# main_board_CHM.net
KiCad netlist of a schematic drawn in Altium Designer
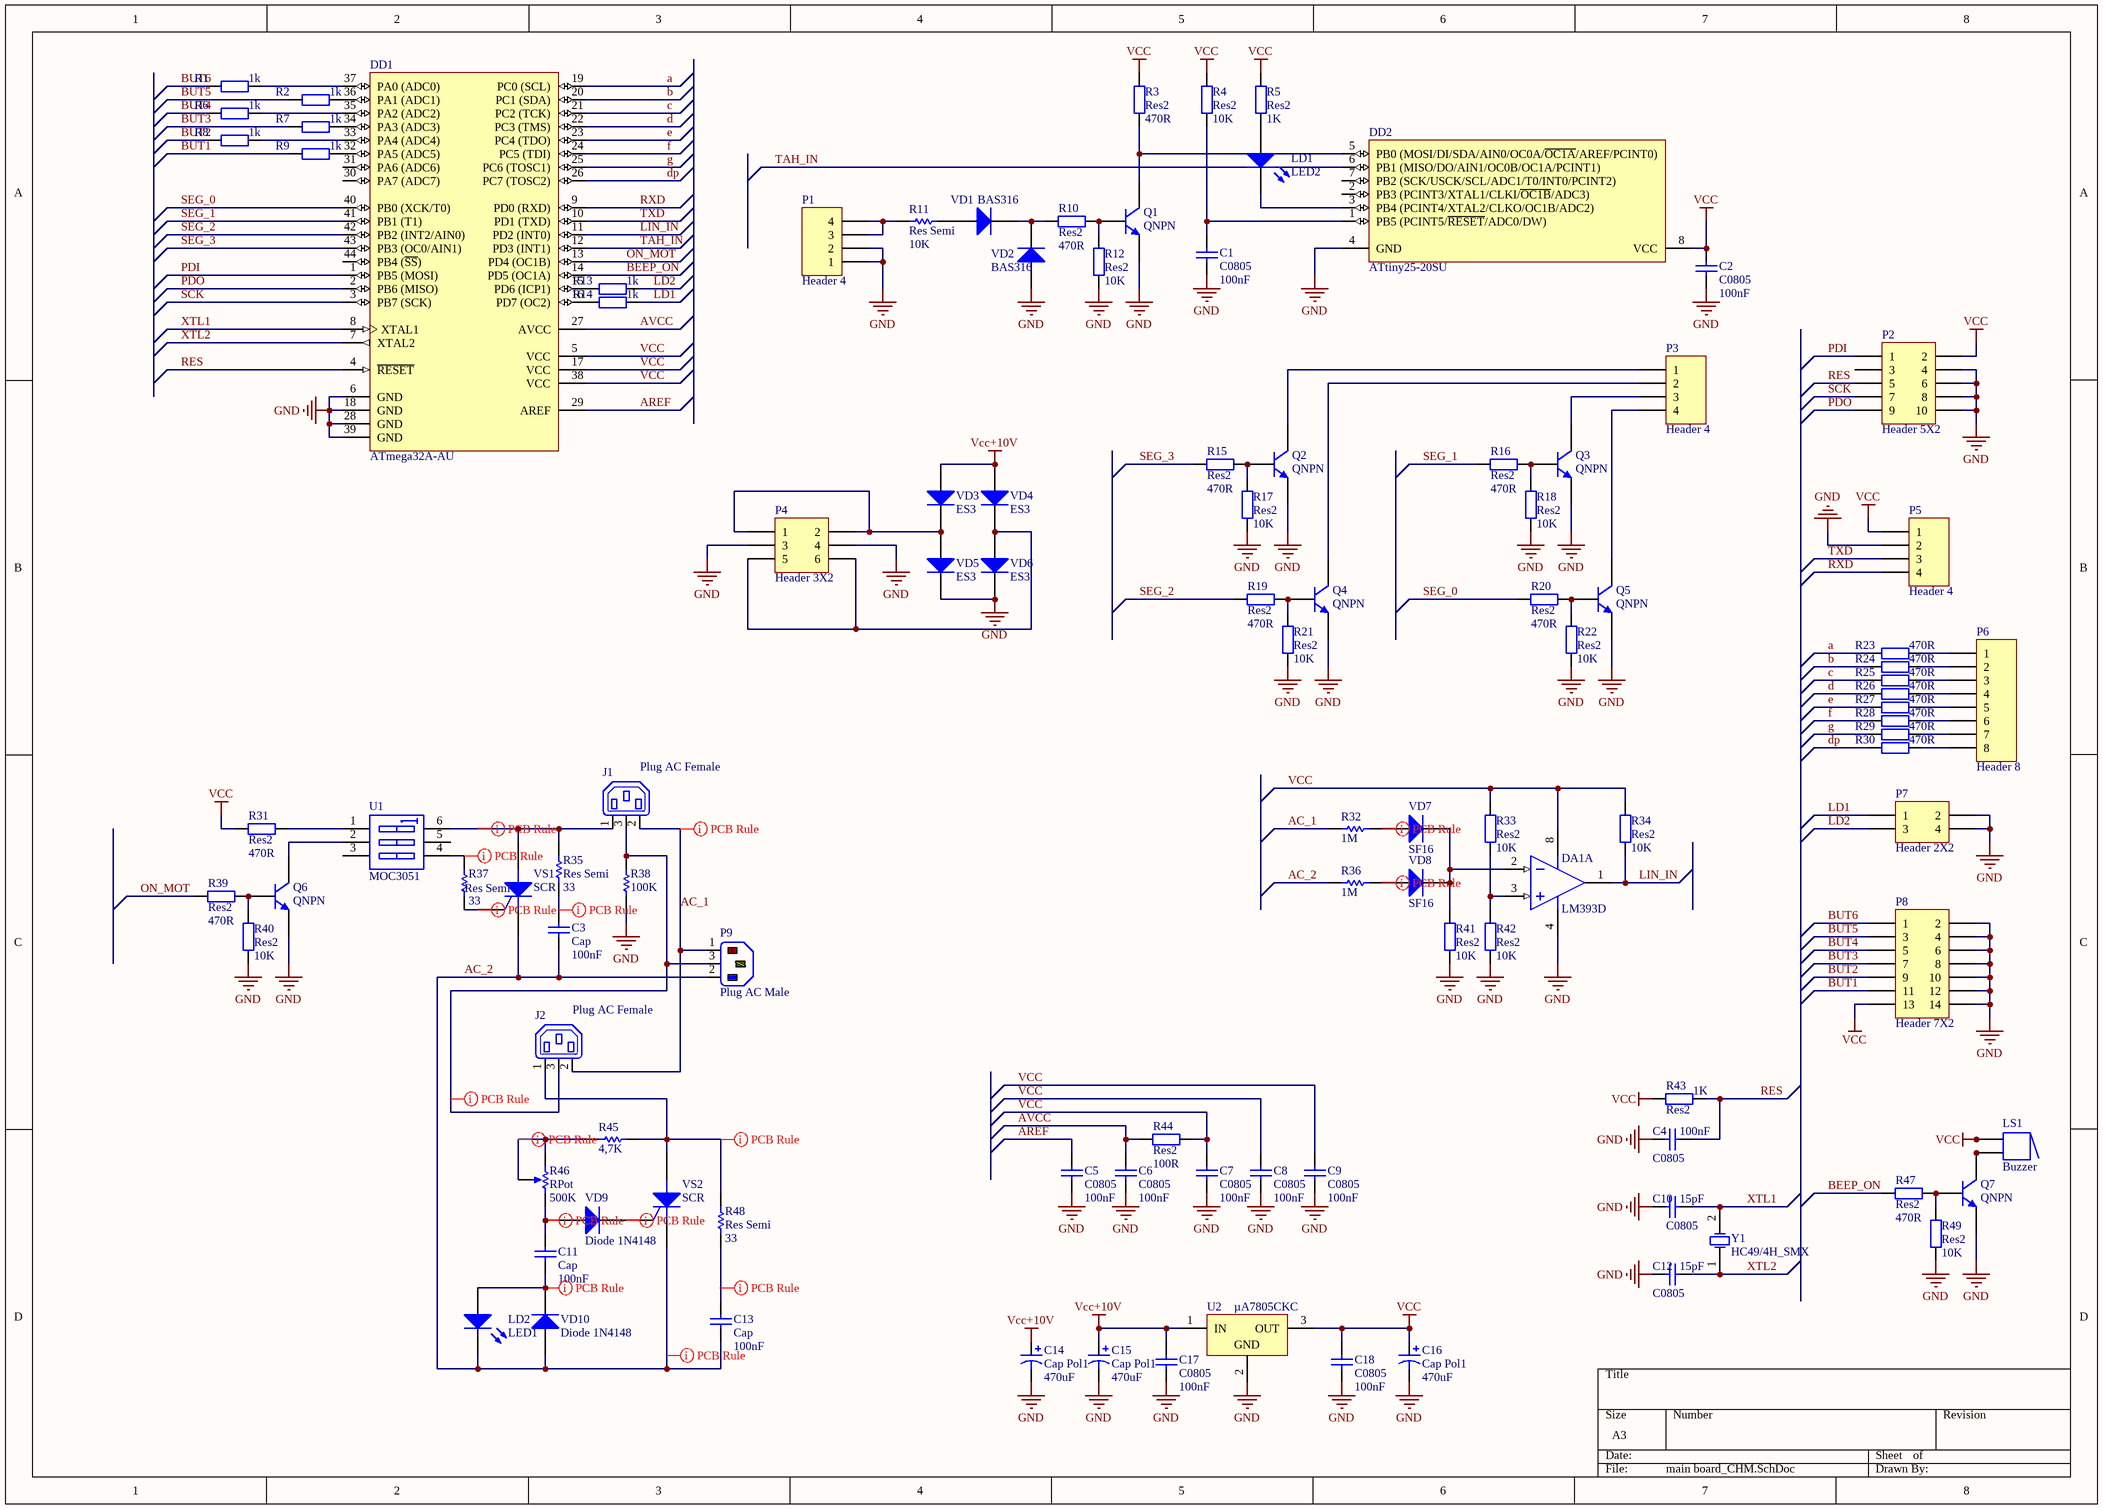
[diagram p0: main board_CHM.SchDoc]

(export (version "E")
  (design (tool "Eeschema 10.0.6"))
  (components
    (comp (ref "C1")
      (value "C0805")
      (footprint "0805")
      (description "Ceramic Chip Capacitor - Standard")
      (fields (field (name "ALTIUM_VALUE") "100nF"))
      (libsource (lib "KEMET Chip Capacitor") (part "C0805"))
    )
    (comp (ref "C2")
      (value "C0805")
      (footprint "0805")
      (description "Ceramic Chip Capacitor - Standard")
      (fields (field (name "ALTIUM_VALUE") "100nF"))
      (libsource (lib "KEMET Chip Capacitor") (part "C0805"))
    )
    (comp (ref "C3")
      (value "Cap")
      (footprint "RAD-0.3")
      (description "Capacitor")
      (fields (field (name "ALTIUM_VALUE") "100nF"))
      (libsource (lib "Miscellaneous Devices") (part "Cap"))
    )
    (comp (ref "C4")
      (value "C0805")
      (footprint "0805")
      (description "Ceramic Chip Capacitor - Standard")
      (fields (field (name "ALTIUM_VALUE") "100nF"))
      (libsource (lib "KEMET Chip Capacitor") (part "C0805"))
    )
    (comp (ref "C5")
      (value "C0805")
      (footprint "0805")
      (description "Ceramic Chip Capacitor - Standard")
      (fields (field (name "ALTIUM_VALUE") "100nF"))
      (libsource (lib "KEMET Chip Capacitor") (part "C0805"))
    )
    (comp (ref "C6")
      (value "C0805")
      (footprint "0805")
      (description "Ceramic Chip Capacitor - Standard")
      (fields (field (name "ALTIUM_VALUE") "100nF"))
      (libsource (lib "KEMET Chip Capacitor") (part "C0805"))
    )
    (comp (ref "C7")
      (value "C0805")
      (footprint "0805")
      (description "Ceramic Chip Capacitor - Standard")
      (fields (field (name "ALTIUM_VALUE") "100nF"))
      (libsource (lib "KEMET Chip Capacitor") (part "C0805"))
    )
    (comp (ref "C8")
      (value "C0805")
      (footprint "0805")
      (description "Ceramic Chip Capacitor - Standard")
      (fields (field (name "ALTIUM_VALUE") "100nF"))
      (libsource (lib "KEMET Chip Capacitor") (part "C0805"))
    )
    (comp (ref "C9")
      (value "C0805")
      (footprint "0805")
      (description "Ceramic Chip Capacitor - Standard")
      (fields (field (name "ALTIUM_VALUE") "100nF"))
      (libsource (lib "KEMET Chip Capacitor") (part "C0805"))
    )
    (comp (ref "C10")
      (value "C0805")
      (footprint "0805")
      (description "Ceramic Chip Capacitor - Standard")
      (fields (field (name "ALTIUM_VALUE") "15pF"))
      (libsource (lib "KEMET Chip Capacitor") (part "C0805"))
    )
    (comp (ref "C11")
      (value "Cap")
      (footprint "RAD-0.3")
      (description "Capacitor")
      (fields (field (name "ALTIUM_VALUE") "100nF"))
      (libsource (lib "Miscellaneous Devices") (part "Cap"))
    )
    (comp (ref "C12")
      (value "C0805")
      (footprint "0805")
      (description "Ceramic Chip Capacitor - Standard")
      (fields (field (name "ALTIUM_VALUE") "15pF"))
      (libsource (lib "KEMET Chip Capacitor") (part "C0805"))
    )
    (comp (ref "C13")
      (value "Cap")
      (footprint "RAD-0.3")
      (description "Capacitor")
      (fields (field (name "ALTIUM_VALUE") "100nF"))
      (libsource (lib "Miscellaneous Devices") (part "Cap"))
    )
    (comp (ref "C14")
      (value "Cap Pol1")
      (footprint "RB5-10.5")
      (description "Polarized Capacitor (Radial)")
      (fields (field (name "ALTIUM_VALUE") "470uF"))
      (libsource (lib "Miscellaneous Devices") (part "Cap Pol1"))
    )
    (comp (ref "C15")
      (value "Cap Pol1")
      (footprint "RB5-10.5")
      (description "Polarized Capacitor (Radial)")
      (fields (field (name "ALTIUM_VALUE") "470uF"))
      (libsource (lib "Miscellaneous Devices") (part "Cap Pol1"))
    )
    (comp (ref "C16")
      (value "Cap Pol1")
      (footprint "RB5-10.5")
      (description "Polarized Capacitor (Radial)")
      (fields (field (name "ALTIUM_VALUE") "470uF"))
      (libsource (lib "Miscellaneous Devices") (part "Cap Pol1"))
    )
    (comp (ref "C17")
      (value "C0805")
      (footprint "0805")
      (description "Ceramic Chip Capacitor - Standard")
      (fields (field (name "ALTIUM_VALUE") "100nF"))
      (libsource (lib "KEMET Chip Capacitor") (part "C0805"))
    )
    (comp (ref "C18")
      (value "C0805")
      (footprint "0805")
      (description "Ceramic Chip Capacitor - Standard")
      (fields (field (name "ALTIUM_VALUE") "100nF"))
      (libsource (lib "KEMET Chip Capacitor") (part "C0805"))
    )
    (comp (ref "DA1")
      (value "LM393D")
      (footprint "SO8_L")
      (description "Low-Power Dual Voltage Comparator")
      (libsource (lib "ST Analog Comparator") (part "LM393D"))
    )
    (comp (ref "DD1")
      (value "ATmega32A-AU")
      (footprint "44A_N")
      (libsource (lib "Atmel Microcontroller 8-Bit megaAVR") (part "ATmega32A-AU"))
    )
    (comp (ref "DD2")
      (value "ATtiny25-20SU")
      (footprint "8S2_N")
      (libsource (lib "Atmel Microcontroller 8-Bit tinyAVR") (part "ATtiny25-20SU"))
    )
    (comp (ref "J1")
      (value "Plug AC Female")
      (footprint "SUPER-247")
      (description "IEC Mains Power Outlet, EN60 320-2-2 F Class I, PC Flange Rear Mount, Chassis Socket")
      (libsource (lib "Miscellaneous Connectors") (part "Plug AC Female"))
    )
    (comp (ref "J2")
      (value "Plug AC Female")
      (footprint "Super-TO-247AC")
      (description "IEC Mains Power Outlet, EN60 320-2-2 F Class I, PC Flange Rear Mount, Chassis Socket")
      (libsource (lib "Miscellaneous Connectors") (part "Plug AC Female"))
    )
    (comp (ref "LD1")
      (value "LED2")
      (footprint "3.2X1.6X1.1")
      (description "Typical RED, GREEN, YELLOW, AMBER GaAs LED")
      (libsource (lib "Miscellaneous Devices") (part "LED2"))
    )
    (comp (ref "LD2")
      (value "LED1")
      (footprint "HDR1X2")
      (description "Typical RED GaAs LED")
      (libsource (lib "Miscellaneous Devices") (part "LED1"))
    )
    (comp (ref "LS1")
      (value "Buzzer")
      (footprint "ABSM-1574")
      (description "Magnetic Transducer Buzzer")
      (libsource (lib "Miscellaneous Devices") (part "Buzzer"))
    )
    (comp (ref "P1")
      (value "Header 4")
      (footprint "HDR1X4")
      (description "Header, 4-Pin")
      (libsource (lib "") (part "Header 4_1"))
    )
    (comp (ref "P2")
      (value "Header 5X2")
      (footprint "HDR2X5")
      (description "Header, 5-Pin, Dual row")
      (libsource (lib "Miscellaneous Connectors") (part "Header 5X2"))
    )
    (comp (ref "P3")
      (value "Header 4")
      (footprint "HDR1X4")
      (description "Header, 4-Pin")
      (libsource (lib "Miscellaneous Connectors") (part "Header 4"))
    )
    (comp (ref "P4")
      (value "Header 3X2")
      (footprint "HDR2X3")
      (description "Header, 3-Pin, Dual row")
      (libsource (lib "Miscellaneous Connectors") (part "Header 3X2"))
    )
    (comp (ref "P5")
      (value "Header 4")
      (footprint "HDR1X4")
      (description "Header, 4-Pin")
      (libsource (lib "Miscellaneous Connectors") (part "Header 4"))
    )
    (comp (ref "P6")
      (value "Header 8")
      (footprint "HDR1X8")
      (description "Header, 8-Pin")
      (libsource (lib "Miscellaneous Connectors") (part "Header 8"))
    )
    (comp (ref "P7")
      (value "Header 2X2")
      (footprint "HDR2X2")
      (description "Header, 2-Pin, Dual row")
      (libsource (lib "Miscellaneous Connectors") (part "Header 2X2"))
    )
    (comp (ref "P8")
      (value "Header 7X2")
      (footprint "HDR2X7")
      (description "Header, 7-Pin, Dual row")
      (libsource (lib "Miscellaneous Connectors") (part "Header 7X2"))
    )
    (comp (ref "P9")
      (value "Plug AC Male")
      (footprint "Super-TO-247AC")
      (description "IEC Mains Power Inlet, EN60 320-1 C14 Class I Cold Condition, PC Flange Rear Mount, Chassis Plug")
      (libsource (lib "Miscellaneous Connectors") (part "Plug AC Male"))
    )
    (comp (ref "Q1")
      (value "QNPN")
      (footprint "SOT23_M")
      (description "NPN Bipolar Transistor")
      (libsource (lib "Miscellaneous Devices") (part "QNPN"))
    )
    (comp (ref "Q2")
      (value "QNPN")
      (footprint "SOT23_M")
      (description "NPN Bipolar Transistor")
      (libsource (lib "Miscellaneous Devices") (part "QNPN"))
    )
    (comp (ref "Q3")
      (value "QNPN")
      (footprint "SOT23_M")
      (description "NPN Bipolar Transistor")
      (libsource (lib "Miscellaneous Devices") (part "QNPN"))
    )
    (comp (ref "Q4")
      (value "QNPN")
      (footprint "SOT23_M")
      (description "NPN Bipolar Transistor")
      (libsource (lib "Miscellaneous Devices") (part "QNPN"))
    )
    (comp (ref "Q5")
      (value "QNPN")
      (footprint "SOT23_M")
      (description "NPN Bipolar Transistor")
      (libsource (lib "Miscellaneous Devices") (part "QNPN"))
    )
    (comp (ref "Q6")
      (value "QNPN")
      (footprint "SOT23_M")
      (description "NPN Bipolar Transistor")
      (libsource (lib "Miscellaneous Devices") (part "QNPN"))
    )
    (comp (ref "Q7")
      (value "QNPN")
      (footprint "SOT23_M")
      (description "NPN Bipolar Transistor")
      (libsource (lib "Miscellaneous Devices") (part "QNPN"))
    )
    (comp (ref "R1")
      (value "1k")
      (footprint "6-0805_N")
      (description "Resistor")
      (fields (field (name "Comment") "Res2"))
      (libsource (lib "Miscellaneous Devices") (part "Res2"))
    )
    (comp (ref "R2")
      (value "1k")
      (footprint "6-0805_N")
      (description "Resistor")
      (fields (field (name "Comment") "Res2"))
      (libsource (lib "Miscellaneous Devices") (part "Res2"))
    )
    (comp (ref "R3")
      (value "Res2")
      (footprint "6-0805_N")
      (description "Resistor")
      (fields (field (name "ALTIUM_VALUE") "470R"))
      (libsource (lib "") (part "Res2_1"))
    )
    (comp (ref "R4")
      (value "Res2")
      (footprint "6-0805_N")
      (description "Resistor")
      (fields (field (name "ALTIUM_VALUE") "10K"))
      (libsource (lib "") (part "Res2_1"))
    )
    (comp (ref "R5")
      (value "Res2")
      (footprint "6-0805_N")
      (description "Resistor")
      (fields (field (name "ALTIUM_VALUE") "1K"))
      (libsource (lib "") (part "Res2_1"))
    )
    (comp (ref "R6")
      (value "1k")
      (footprint "6-0805_N")
      (description "Resistor")
      (fields (field (name "Comment") "Res2"))
      (libsource (lib "Miscellaneous Devices") (part "Res2"))
    )
    (comp (ref "R7")
      (value "1k")
      (footprint "6-0805_N")
      (description "Resistor")
      (fields (field (name "Comment") "Res2"))
      (libsource (lib "Miscellaneous Devices") (part "Res2"))
    )
    (comp (ref "R8")
      (value "1k")
      (footprint "6-0805_N")
      (description "Resistor")
      (fields (field (name "Comment") "Res2"))
      (libsource (lib "Miscellaneous Devices") (part "Res2"))
    )
    (comp (ref "R9")
      (value "1k")
      (footprint "6-0805_N")
      (description "Resistor")
      (fields (field (name "Comment") "Res2"))
      (libsource (lib "Miscellaneous Devices") (part "Res2"))
    )
    (comp (ref "R10")
      (value "Res2")
      (footprint "6-0805_N")
      (description "Resistor")
      (fields (field (name "ALTIUM_VALUE") "470R"))
      (libsource (lib "Miscellaneous Devices") (part "Res2"))
    )
    (comp (ref "R11")
      (value "Res Semi")
      (footprint "AXIAL-0.5")
      (description "Semiconductor Resistor")
      (fields (field (name "ALTIUM_VALUE") "10K"))
      (libsource (lib "Miscellaneous Devices") (part "Res Semi"))
    )
    (comp (ref "R12")
      (value "Res2")
      (footprint "6-0805_N")
      (description "Resistor")
      (fields (field (name "ALTIUM_VALUE") "10K"))
      (libsource (lib "") (part "Res2_1"))
    )
    (comp (ref "R13")
      (value "1k")
      (footprint "6-0805_N")
      (description "Resistor")
      (fields (field (name "Comment") "Res2"))
      (libsource (lib "Miscellaneous Devices") (part "Res2"))
    )
    (comp (ref "R14")
      (value "1k")
      (footprint "6-0805_N")
      (description "Resistor")
      (fields (field (name "Comment") "Res2"))
      (libsource (lib "Miscellaneous Devices") (part "Res2"))
    )
    (comp (ref "R15")
      (value "Res2")
      (footprint "6-0805_N")
      (description "Resistor")
      (fields (field (name "ALTIUM_VALUE") "470R"))
      (libsource (lib "Miscellaneous Devices") (part "Res2"))
    )
    (comp (ref "R16")
      (value "Res2")
      (footprint "6-0805_N")
      (description "Resistor")
      (fields (field (name "ALTIUM_VALUE") "470R"))
      (libsource (lib "Miscellaneous Devices") (part "Res2"))
    )
    (comp (ref "R17")
      (value "Res2")
      (footprint "6-0805_N")
      (description "Resistor")
      (fields (field (name "ALTIUM_VALUE") "10K"))
      (libsource (lib "") (part "Res2_1"))
    )
    (comp (ref "R18")
      (value "Res2")
      (footprint "6-0805_N")
      (description "Resistor")
      (fields (field (name "ALTIUM_VALUE") "10K"))
      (libsource (lib "") (part "Res2_1"))
    )
    (comp (ref "R19")
      (value "Res2")
      (footprint "6-0805_N")
      (description "Resistor")
      (fields (field (name "ALTIUM_VALUE") "470R"))
      (libsource (lib "Miscellaneous Devices") (part "Res2"))
    )
    (comp (ref "R20")
      (value "Res2")
      (footprint "6-0805_N")
      (description "Resistor")
      (fields (field (name "ALTIUM_VALUE") "470R"))
      (libsource (lib "Miscellaneous Devices") (part "Res2"))
    )
    (comp (ref "R21")
      (value "Res2")
      (footprint "6-0805_N")
      (description "Resistor")
      (fields (field (name "ALTIUM_VALUE") "10K"))
      (libsource (lib "") (part "Res2_1"))
    )
    (comp (ref "R22")
      (value "Res2")
      (footprint "6-0805_N")
      (description "Resistor")
      (fields (field (name "ALTIUM_VALUE") "10K"))
      (libsource (lib "") (part "Res2_1"))
    )
    (comp (ref "R23")
      (value "470R")
      (footprint "6-0805_N")
      (description "Resistor")
      (fields (field (name "Comment") "Res2"))
      (libsource (lib "Miscellaneous Devices") (part "Res2"))
    )
    (comp (ref "R24")
      (value "470R")
      (footprint "6-0805_N")
      (description "Resistor")
      (fields (field (name "Comment") "Res2"))
      (libsource (lib "Miscellaneous Devices") (part "Res2"))
    )
    (comp (ref "R25")
      (value "470R")
      (footprint "6-0805_N")
      (description "Resistor")
      (fields (field (name "Comment") "Res2"))
      (libsource (lib "Miscellaneous Devices") (part "Res2"))
    )
    (comp (ref "R26")
      (value "470R")
      (footprint "6-0805_N")
      (description "Resistor")
      (fields (field (name "Comment") "Res2"))
      (libsource (lib "Miscellaneous Devices") (part "Res2"))
    )
    (comp (ref "R27")
      (value "470R")
      (footprint "6-0805_N")
      (description "Resistor")
      (fields (field (name "Comment") "Res2"))
      (libsource (lib "Miscellaneous Devices") (part "Res2"))
    )
    (comp (ref "R28")
      (value "470R")
      (footprint "6-0805_N")
      (description "Resistor")
      (fields (field (name "Comment") "Res2"))
      (libsource (lib "Miscellaneous Devices") (part "Res2"))
    )
    (comp (ref "R29")
      (value "470R")
      (footprint "6-0805_N")
      (description "Resistor")
      (fields (field (name "Comment") "Res2"))
      (libsource (lib "Miscellaneous Devices") (part "Res2"))
    )
    (comp (ref "R30")
      (value "470R")
      (footprint "6-0805_N")
      (description "Resistor")
      (fields (field (name "Comment") "Res2"))
      (libsource (lib "Miscellaneous Devices") (part "Res2"))
    )
    (comp (ref "R31")
      (value "Res2")
      (footprint "6-0805_N")
      (description "Resistor")
      (fields (field (name "ALTIUM_VALUE") "470R"))
      (libsource (lib "Miscellaneous Devices") (part "Res2"))
    )
    (comp (ref "R32")
      (value "1M")
      (footprint "AXIAL-0.5")
      (description "Semiconductor Resistor")
      (fields (field (name "Comment") "Res Semi"))
      (libsource (lib "Miscellaneous Devices") (part "Res Semi"))
    )
    (comp (ref "R33")
      (value "Res2")
      (footprint "6-0805_N")
      (description "Resistor")
      (fields (field (name "ALTIUM_VALUE") "10K"))
      (libsource (lib "") (part "Res2_1"))
    )
    (comp (ref "R34")
      (value "Res2")
      (footprint "6-0805_N")
      (description "Resistor")
      (fields (field (name "ALTIUM_VALUE") "10K"))
      (libsource (lib "") (part "Res2_1"))
    )
    (comp (ref "R35")
      (value "Res Semi")
      (footprint "AXIAL-0.5")
      (description "Semiconductor Resistor")
      (fields (field (name "ALTIUM_VALUE") "33"))
      (libsource (lib "Miscellaneous Devices") (part "Res Semi"))
    )
    (comp (ref "R36")
      (value "1M")
      (footprint "AXIAL-0.5")
      (description "Semiconductor Resistor")
      (fields (field (name "Comment") "Res Semi"))
      (libsource (lib "Miscellaneous Devices") (part "Res Semi"))
    )
    (comp (ref "R37")
      (value "Res Semi")
      (footprint "AXIAL-0.5")
      (description "Semiconductor Resistor")
      (fields (field (name "ALTIUM_VALUE") "33"))
      (libsource (lib "Miscellaneous Devices") (part "Res Semi"))
    )
    (comp (ref "R38")
      (value "100K")
      (footprint "AXIAL-0.5")
      (description "Semiconductor Resistor")
      (fields (field (name "Comment") "Res Semi"))
      (libsource (lib "Miscellaneous Devices") (part "Res Semi"))
    )
    (comp (ref "R39")
      (value "Res2")
      (footprint "6-0805_N")
      (description "Resistor")
      (fields (field (name "ALTIUM_VALUE") "470R"))
      (libsource (lib "Miscellaneous Devices") (part "Res2"))
    )
    (comp (ref "R40")
      (value "Res2")
      (footprint "6-0805_N")
      (description "Resistor")
      (fields (field (name "ALTIUM_VALUE") "10K"))
      (libsource (lib "") (part "Res2_1"))
    )
    (comp (ref "R41")
      (value "Res2")
      (footprint "6-0805_N")
      (description "Resistor")
      (fields (field (name "ALTIUM_VALUE") "10K"))
      (libsource (lib "") (part "Res2_1"))
    )
    (comp (ref "R42")
      (value "Res2")
      (footprint "6-0805_N")
      (description "Resistor")
      (fields (field (name "ALTIUM_VALUE") "10K"))
      (libsource (lib "") (part "Res2_1"))
    )
    (comp (ref "R43")
      (value "Res2")
      (footprint "6-0805_N")
      (description "Resistor")
      (fields (field (name "ALTIUM_VALUE") "1K"))
      (libsource (lib "Miscellaneous Devices") (part "Res2"))
    )
    (comp (ref "R44")
      (value "Res2")
      (footprint "6-0805_N")
      (description "Resistor")
      (fields (field (name "ALTIUM_VALUE") "100R"))
      (libsource (lib "Miscellaneous Devices") (part "Res2"))
    )
    (comp (ref "R45")
      (value "4,7K")
      (footprint "AXIAL-0.5")
      (description "Semiconductor Resistor")
      (fields (field (name "Comment") "Res Semi"))
      (libsource (lib "Miscellaneous Devices") (part "Res Semi"))
    )
    (comp (ref "R46")
      (value "RPot")
      (footprint "VR5")
      (description "Potentiometer")
      (fields (field (name "ALTIUM_VALUE") "500K"))
      (libsource (lib "Miscellaneous Devices") (part "RPot"))
    )
    (comp (ref "R47")
      (value "Res2")
      (footprint "6-0805_N")
      (description "Resistor")
      (fields (field (name "ALTIUM_VALUE") "470R"))
      (libsource (lib "Miscellaneous Devices") (part "Res2"))
    )
    (comp (ref "R48")
      (value "Res Semi")
      (footprint "AXIAL-0.5")
      (description "Semiconductor Resistor")
      (fields (field (name "ALTIUM_VALUE") "33"))
      (libsource (lib "Miscellaneous Devices") (part "Res Semi"))
    )
    (comp (ref "R49")
      (value "Res2")
      (footprint "6-0805_N")
      (description "Resistor")
      (fields (field (name "ALTIUM_VALUE") "10K"))
      (libsource (lib "") (part "Res2_1"))
    )
    (comp (ref "U1")
      (value "MOC3051")
      (footprint "DIP-6")
      (description "DIP Switch, 3 Position, SPST")
      (libsource (lib "Miscellaneous Devices") (part "SW DIP-3"))
    )
    (comp (ref "U2")
      (value "µA7805CKC")
      (footprint "KC03")
      (description "Positive-Voltage Regulator")
      (libsource (lib "TI Power Mgt Voltage Regulator") (part "µA7805CKC"))
    )
    (comp (ref "VD1")
      (value "BAS316")
      (footprint "SOD-323")
      (description "Silicon RF Switching Diode for VHF Band Switching in TV/VTR Tuners")
      (libsource (lib "Infineon Discrete Diode") (part "BA592"))
    )
    (comp (ref "VD2")
      (value "BAS316")
      (footprint "SOD-323")
      (description "Silicon RF Switching Diode for VHF Band Switching in TV/VTR Tuners")
      (libsource (lib "Infineon Discrete Diode") (part "BA592"))
    )
    (comp (ref "VD3")
      (value "ES3")
      (footprint "SMC")
      (description "Silicon RF Switching Diode for VHF Band Switching in TV/VTR Tuners")
      (libsource (lib "Infineon Discrete Diode") (part "BA592"))
    )
    (comp (ref "VD4")
      (value "ES3")
      (footprint "SMC")
      (description "Silicon RF Switching Diode for VHF Band Switching in TV/VTR Tuners")
      (libsource (lib "Infineon Discrete Diode") (part "BA592"))
    )
    (comp (ref "VD5")
      (value "ES3")
      (footprint "SMC")
      (description "Silicon RF Switching Diode for VHF Band Switching in TV/VTR Tuners")
      (libsource (lib "Infineon Discrete Diode") (part "BA592"))
    )
    (comp (ref "VD6")
      (value "ES3")
      (footprint "SMC")
      (description "Silicon RF Switching Diode for VHF Band Switching in TV/VTR Tuners")
      (libsource (lib "Infineon Discrete Diode") (part "BA592"))
    )
    (comp (ref "VD7")
      (value "SF16")
      (footprint "DO-41")
      (description "1 Amp General Purpose Rectifier")
      (libsource (lib "Miscellaneous Devices") (part "Diode 1N4001"))
    )
    (comp (ref "VD8")
      (value "SF16")
      (footprint "DO-41")
      (description "1 Amp General Purpose Rectifier")
      (libsource (lib "Miscellaneous Devices") (part "Diode 1N4001"))
    )
    (comp (ref "VD9")
      (value "Diode 1N4148")
      (footprint "DO-35")
      (description "High Conductance Fast Diode")
      (libsource (lib "Miscellaneous Devices") (part "Diode 1N4148"))
    )
    (comp (ref "VD10")
      (value "Diode 1N4148")
      (footprint "DO-35")
      (description "High Conductance Fast Diode")
      (libsource (lib "Miscellaneous Devices") (part "Diode 1N4148"))
    )
    (comp (ref "VS1")
      (value "SCR")
      (footprint "Super-TO-247AC")
      (description "Silicon Controlled Rectifier")
      (libsource (lib "Miscellaneous Devices") (part "SCR"))
    )
    (comp (ref "VS2")
      (value "SCR")
      (footprint "Super-TO-247AC")
      (description "Silicon Controlled Rectifier")
      (libsource (lib "Miscellaneous Devices") (part "SCR"))
    )
    (comp (ref "Y1")
      (value "HC49/4H_SMX")
      (footprint "HC49/4H_SMX")
      (description "Surface Mount Quartz Crystal")
      (libsource (lib "C-MAC Crystal Oscillator") (part "HC49/4H_SMX"))
    )
  )
  (nets
    (net (code "1") (name "/AC_1") (class "Default")
      (node (ref "J1") (pin "2") (pinfunction "N_2") (pintype "power_in"))
      (node (ref "J2") (pin "2") (pinfunction "N_2") (pintype "power_in"))
      (node (ref "P9") (pin "1") (pinfunction "L_1") (pintype "power_in"))
      (node (ref "R32") (pin "1") (pinfunction "1_1") (pintype "passive"))
    )
    (net (code "2") (name "/AC_2") (class "Default")
      (node (ref "C13") (pin "1") (pinfunction "1_1") (pintype "passive"))
      (node (ref "C3") (pin "1") (pinfunction "1_1") (pintype "passive"))
      (node (ref "LD2") (pin "2") (pinfunction "K_2") (pintype "passive"))
      (node (ref "P9") (pin "2") (pinfunction "N_2") (pintype "power_in"))
      (node (ref "R36") (pin "1") (pinfunction "1_1") (pintype "passive"))
      (node (ref "VD10") (pin "1") (pinfunction "A_1") (pintype "passive"))
      (node (ref "VS1") (pin "3") (pinfunction "K_3") (pintype "passive"))
      (node (ref "VS2") (pin "3") (pinfunction "K_3") (pintype "passive"))
    )
    (net (code "3") (name "/AREF") (class "Default")
      (node (ref "C5") (pin "2") (pinfunction "2_2") (pintype "passive"))
      (node (ref "DD1") (pin "29") (pinfunction "AREF_29") (pintype "power_in"))
    )
    (net (code "4") (name "/AVCC") (class "Default")
      (node (ref "C6") (pin "2") (pinfunction "2_2") (pintype "passive"))
      (node (ref "DD1") (pin "27") (pinfunction "AVCC_27") (pintype "power_in"))
      (node (ref "R44") (pin "1") (pinfunction "1_1") (pintype "passive"))
    )
    (net (code "5") (name "/BEEP_ON") (class "Default")
      (node (ref "DD1") (pin "14") (pinfunction "PD5_(OC1A)_14") (pintype "bidirectional"))
      (node (ref "R47") (pin "1") (pinfunction "1_1") (pintype "passive"))
    )
    (net (code "6") (name "/BUT1") (class "Default")
      (node (ref "P8") (pin "11") (pinfunction "11_11") (pintype "passive"))
      (node (ref "R9") (pin "1") (pinfunction "1_1") (pintype "passive"))
    )
    (net (code "7") (name "/BUT2") (class "Default")
      (node (ref "P8") (pin "9") (pinfunction "9_9") (pintype "passive"))
      (node (ref "R8") (pin "1") (pinfunction "1_1") (pintype "passive"))
    )
    (net (code "8") (name "/BUT3") (class "Default")
      (node (ref "P8") (pin "7") (pinfunction "7_7") (pintype "passive"))
      (node (ref "R7") (pin "1") (pinfunction "1_1") (pintype "passive"))
    )
    (net (code "9") (name "/BUT4") (class "Default")
      (node (ref "P8") (pin "5") (pinfunction "5_5") (pintype "passive"))
      (node (ref "R6") (pin "1") (pinfunction "1_1") (pintype "passive"))
    )
    (net (code "10") (name "/BUT5") (class "Default")
      (node (ref "P8") (pin "3") (pinfunction "3_3") (pintype "passive"))
      (node (ref "R2") (pin "1") (pinfunction "1_1") (pintype "passive"))
    )
    (net (code "11") (name "/BUT6") (class "Default")
      (node (ref "P8") (pin "1") (pinfunction "1_1") (pintype "passive"))
      (node (ref "R1") (pin "1") (pinfunction "1_1") (pintype "passive"))
    )
    (net (code "12") (name "/LD1") (class "Default")
      (node (ref "P7") (pin "1") (pinfunction "1_1") (pintype "passive"))
      (node (ref "R14") (pin "2") (pinfunction "2_2") (pintype "passive"))
    )
    (net (code "13") (name "/LD2") (class "Default")
      (node (ref "P7") (pin "3") (pinfunction "3_3") (pintype "passive"))
      (node (ref "R13") (pin "2") (pinfunction "2_2") (pintype "passive"))
    )
    (net (code "14") (name "/LIN_IN") (class "Default")
      (node (ref "DA1") (pin "1") (pinfunction "OUT_1") (pintype "open_collector"))
      (node (ref "DD1") (pin "11") (pinfunction "PD2_(INT0)_11") (pintype "bidirectional"))
      (node (ref "R34") (pin "1") (pinfunction "1_1") (pintype "passive"))
    )
    (net (code "15") (name "/ON_MOT") (class "Default")
      (node (ref "DD1") (pin "13") (pinfunction "PD4_(OC1B)_13") (pintype "bidirectional"))
      (node (ref "R39") (pin "1") (pinfunction "1_1") (pintype "passive"))
    )
    (net (code "16") (name "/PDI") (class "Default")
      (node (ref "DD1") (pin "1") (pinfunction "PB5_(MOSI)_1") (pintype "bidirectional"))
      (node (ref "P2") (pin "1") (pinfunction "1_1") (pintype "passive"))
    )
    (net (code "17") (name "/PDO") (class "Default")
      (node (ref "DD1") (pin "2") (pinfunction "PB6_(MISO)_2") (pintype "bidirectional"))
      (node (ref "P2") (pin "9") (pinfunction "9_9") (pintype "passive"))
    )
    (net (code "18") (name "/RES") (class "Default")
      (node (ref "C4") (pin "2") (pinfunction "2_2") (pintype "passive"))
      (node (ref "DD1") (pin "4") (pinfunction "~{RESET}_4") (pintype "input"))
      (node (ref "P2") (pin "5") (pinfunction "5_5") (pintype "passive"))
      (node (ref "R43") (pin "2") (pinfunction "2_2") (pintype "passive"))
    )
    (net (code "19") (name "/RXD") (class "Default")
      (node (ref "DD1") (pin "9") (pinfunction "PD0_(RXD)_9") (pintype "bidirectional"))
      (node (ref "P5") (pin "4") (pinfunction "4_4") (pintype "passive"))
    )
    (net (code "20") (name "/SCK") (class "Default")
      (node (ref "DD1") (pin "3") (pinfunction "PB7_(SCK)_3") (pintype "bidirectional"))
      (node (ref "P2") (pin "7") (pinfunction "7_7") (pintype "passive"))
    )
    (net (code "21") (name "/SEG_0") (class "Default")
      (node (ref "DD1") (pin "40") (pinfunction "PB0_(XCK/T0)_40") (pintype "bidirectional"))
      (node (ref "R20") (pin "1") (pinfunction "1_1") (pintype "passive"))
    )
    (net (code "22") (name "/SEG_1") (class "Default")
      (node (ref "DD1") (pin "41") (pinfunction "PB1_(T1)_41") (pintype "bidirectional"))
      (node (ref "R16") (pin "1") (pinfunction "1_1") (pintype "passive"))
    )
    (net (code "23") (name "/SEG_2") (class "Default")
      (node (ref "DD1") (pin "42") (pinfunction "PB2_(INT2/AIN0)_42") (pintype "bidirectional"))
      (node (ref "R19") (pin "1") (pinfunction "1_1") (pintype "passive"))
    )
    (net (code "24") (name "/SEG_3") (class "Default")
      (node (ref "DD1") (pin "43") (pinfunction "PB3_(OC0/AIN1)_43") (pintype "bidirectional"))
      (node (ref "R15") (pin "1") (pinfunction "1_1") (pintype "passive"))
    )
    (net (code "25") (name "/TAH_IN") (class "Default")
      (node (ref "DD1") (pin "12") (pinfunction "PD3_(INT1)_12") (pintype "bidirectional"))
      (node (ref "DD2") (pin "6") (pinfunction "PB1_(MISO/DO/AIN1/OC0B/OC1A/PCINT1)_6") (pintype "bidirectional"))
    )
    (net (code "26") (name "/TXD") (class "Default")
      (node (ref "DD1") (pin "10") (pinfunction "PD1_(TXD)_10") (pintype "bidirectional"))
      (node (ref "P5") (pin "3") (pinfunction "3_3") (pintype "passive"))
    )
    (net (code "27") (name "/XTL1") (class "Default")
      (node (ref "C10") (pin "2") (pinfunction "2_2") (pintype "passive"))
      (node (ref "DD1") (pin "8") (pinfunction "XTAL1_8") (pintype "input"))
      (node (ref "Y1") (pin "2") (pinfunction "OSC2_2") (pintype "passive"))
    )
    (net (code "28") (name "/XTL2") (class "Default")
      (node (ref "C12") (pin "2") (pinfunction "2_2") (pintype "passive"))
      (node (ref "DD1") (pin "7") (pinfunction "XTAL2_7") (pintype "output"))
      (node (ref "Y1") (pin "1") (pinfunction "OSC1_1") (pintype "passive"))
    )
    (net (code "29") (name "/a") (class "Default")
      (node (ref "DD1") (pin "19") (pinfunction "PC0_(SCL)_19") (pintype "bidirectional"))
      (node (ref "R23") (pin "1") (pinfunction "1_1") (pintype "passive"))
    )
    (net (code "30") (name "/b") (class "Default")
      (node (ref "DD1") (pin "20") (pinfunction "PC1_(SDA)_20") (pintype "bidirectional"))
      (node (ref "R24") (pin "1") (pinfunction "1_1") (pintype "passive"))
    )
    (net (code "31") (name "/c") (class "Default")
      (node (ref "DD1") (pin "21") (pinfunction "PC2_(TCK)_21") (pintype "bidirectional"))
      (node (ref "R25") (pin "1") (pinfunction "1_1") (pintype "passive"))
    )
    (net (code "32") (name "/d") (class "Default")
      (node (ref "DD1") (pin "22") (pinfunction "PC3_(TMS)_22") (pintype "bidirectional"))
      (node (ref "R26") (pin "1") (pinfunction "1_1") (pintype "passive"))
    )
    (net (code "33") (name "/dp") (class "Default")
      (node (ref "DD1") (pin "26") (pinfunction "PC7_(TOSC2)_26") (pintype "bidirectional"))
      (node (ref "R30") (pin "1") (pinfunction "1_1") (pintype "passive"))
    )
    (net (code "34") (name "/e") (class "Default")
      (node (ref "DD1") (pin "23") (pinfunction "PC4_(TDO)_23") (pintype "bidirectional"))
      (node (ref "R27") (pin "1") (pinfunction "1_1") (pintype "passive"))
    )
    (net (code "35") (name "/f") (class "Default")
      (node (ref "DD1") (pin "24") (pinfunction "PC5_(TDI)_24") (pintype "bidirectional"))
      (node (ref "R28") (pin "1") (pinfunction "1_1") (pintype "passive"))
    )
    (net (code "36") (name "/g") (class "Default")
      (node (ref "DD1") (pin "25") (pinfunction "PC6_(TOSC1)_25") (pintype "bidirectional"))
      (node (ref "R29") (pin "1") (pinfunction "1_1") (pintype "passive"))
    )
    (net (code "37") (name "GND") (class "Default")
      (node (ref "C1") (pin "1") (pinfunction "1_1") (pintype "passive"))
      (node (ref "C10") (pin "1") (pinfunction "1_1") (pintype "passive"))
      (node (ref "C12") (pin "1") (pinfunction "1_1") (pintype "passive"))
      (node (ref "C14") (pin "2") (pinfunction "2_2") (pintype "passive"))
      (node (ref "C15") (pin "2") (pinfunction "2_2") (pintype "passive"))
      (node (ref "C16") (pin "2") (pinfunction "2_2") (pintype "passive"))
      (node (ref "C17") (pin "1") (pinfunction "1_1") (pintype "passive"))
      (node (ref "C18") (pin "1") (pinfunction "1_1") (pintype "passive"))
      (node (ref "C2") (pin "1") (pinfunction "1_1") (pintype "passive"))
      (node (ref "C4") (pin "1") (pinfunction "1_1") (pintype "passive"))
      (node (ref "C5") (pin "1") (pinfunction "1_1") (pintype "passive"))
      (node (ref "C6") (pin "1") (pinfunction "1_1") (pintype "passive"))
      (node (ref "C7") (pin "1") (pinfunction "1_1") (pintype "passive"))
      (node (ref "C8") (pin "1") (pinfunction "1_1") (pintype "passive"))
      (node (ref "C9") (pin "1") (pinfunction "1_1") (pintype "passive"))
      (node (ref "DA1") (pin "4") (pinfunction "V-_4") (pintype "power_in"))
      (node (ref "DD1") (pin "18") (pinfunction "GND_18") (pintype "power_in"))
      (node (ref "DD1") (pin "28") (pinfunction "GND_28") (pintype "power_in"))
      (node (ref "DD1") (pin "39") (pinfunction "GND_39") (pintype "power_in"))
      (node (ref "DD1") (pin "6") (pinfunction "GND_6") (pintype "power_in"))
      (node (ref "DD2") (pin "4") (pinfunction "GND_4") (pintype "power_in"))
      (node (ref "P1") (pin "1") (pinfunction "1_1") (pintype "passive"))
      (node (ref "P1") (pin "2") (pinfunction "2_2") (pintype "passive"))
      (node (ref "P2") (pin "10") (pinfunction "10_10") (pintype "passive"))
      (node (ref "P2") (pin "4") (pinfunction "4_4") (pintype "passive"))
      (node (ref "P2") (pin "6") (pinfunction "6_6") (pintype "passive"))
      (node (ref "P2") (pin "8") (pinfunction "8_8") (pintype "passive"))
      (node (ref "P4") (pin "3") (pinfunction "3_3") (pintype "passive"))
      (node (ref "P4") (pin "4") (pinfunction "4_4") (pintype "passive"))
      (node (ref "P5") (pin "2") (pinfunction "2_2") (pintype "passive"))
      (node (ref "P7") (pin "2") (pinfunction "2_2") (pintype "passive"))
      (node (ref "P7") (pin "4") (pinfunction "4_4") (pintype "passive"))
      (node (ref "P8") (pin "10") (pinfunction "10_10") (pintype "passive"))
      (node (ref "P8") (pin "12") (pinfunction "12_12") (pintype "passive"))
      (node (ref "P8") (pin "14") (pinfunction "14_14") (pintype "passive"))
      (node (ref "P8") (pin "2") (pinfunction "2_2") (pintype "passive"))
      (node (ref "P8") (pin "4") (pinfunction "4_4") (pintype "passive"))
      (node (ref "P8") (pin "6") (pinfunction "6_6") (pintype "passive"))
      (node (ref "P8") (pin "8") (pinfunction "8_8") (pintype "passive"))
      (node (ref "Q1") (pin "3") (pinfunction "E_3") (pintype "passive"))
      (node (ref "Q2") (pin "3") (pinfunction "E_3") (pintype "passive"))
      (node (ref "Q3") (pin "3") (pinfunction "E_3") (pintype "passive"))
      (node (ref "Q4") (pin "3") (pinfunction "E_3") (pintype "passive"))
      (node (ref "Q5") (pin "3") (pinfunction "E_3") (pintype "passive"))
      (node (ref "Q6") (pin "3") (pinfunction "E_3") (pintype "passive"))
      (node (ref "Q7") (pin "3") (pinfunction "E_3") (pintype "passive"))
      (node (ref "R12") (pin "1") (pinfunction "1_1") (pintype "passive"))
      (node (ref "R17") (pin "1") (pinfunction "1_1") (pintype "passive"))
      (node (ref "R18") (pin "1") (pinfunction "1_1") (pintype "passive"))
      (node (ref "R21") (pin "1") (pinfunction "1_1") (pintype "passive"))
      (node (ref "R22") (pin "1") (pinfunction "1_1") (pintype "passive"))
      (node (ref "R38") (pin "1") (pinfunction "1_1") (pintype "passive"))
      (node (ref "R40") (pin "1") (pinfunction "1_1") (pintype "passive"))
      (node (ref "R41") (pin "1") (pinfunction "1_1") (pintype "passive"))
      (node (ref "R42") (pin "1") (pinfunction "1_1") (pintype "passive"))
      (node (ref "R49") (pin "1") (pinfunction "1_1") (pintype "passive"))
      (node (ref "U2") (pin "2") (pinfunction "GND_2") (pintype "power_in"))
      (node (ref "VD2") (pin "2") (pinfunction "A_2") (pintype "passive"))
      (node (ref "VD5") (pin "1") (pinfunction "K_1") (pintype "passive"))
      (node (ref "VD6") (pin "1") (pinfunction "K_1") (pintype "passive"))
    )
    (net (code "38") (name "Net-(C3-Pad2)") (class "Default")
      (node (ref "C3") (pin "2") (pinfunction "2_2") (pintype "passive"))
      (node (ref "R35") (pin "1") (pinfunction "1_1") (pintype "passive"))
    )
    (net (code "39") (name "Net-(C13-Pad2)") (class "Default")
      (node (ref "C13") (pin "2") (pinfunction "2_2") (pintype "passive"))
      (node (ref "R48") (pin "1") (pinfunction "1_1") (pintype "passive"))
    )
    (net (code "40") (name "Net-(DA1A-IN+)") (class "Default")
      (node (ref "DA1") (pin "3") (pinfunction "IN+_3") (pintype "input"))
      (node (ref "R33") (pin "1") (pinfunction "1_1") (pintype "passive"))
      (node (ref "R42") (pin "2") (pinfunction "2_2") (pintype "passive"))
    )
    (net (code "41") (name "Net-(DA1A-IN-)") (class "Default")
      (node (ref "DA1") (pin "2") (pinfunction "IN-_2") (pintype "input"))
      (node (ref "R41") (pin "2") (pinfunction "2_2") (pintype "passive"))
      (node (ref "VD7") (pin "2") (pinfunction "K_2") (pintype "passive"))
      (node (ref "VD8") (pin "2") (pinfunction "K_2") (pintype "passive"))
    )
    (net (code "42") (name "Net-(DD1-PA0_(ADC0))") (class "Default")
      (node (ref "DD1") (pin "37") (pinfunction "PA0_(ADC0)_37") (pintype "bidirectional"))
      (node (ref "R1") (pin "2") (pinfunction "2_2") (pintype "passive"))
    )
    (net (code "43") (name "Net-(DD1-PA1_(ADC1))") (class "Default")
      (node (ref "DD1") (pin "36") (pinfunction "PA1_(ADC1)_36") (pintype "bidirectional"))
      (node (ref "R2") (pin "2") (pinfunction "2_2") (pintype "passive"))
    )
    (net (code "44") (name "Net-(DD1-PA2_(ADC2))") (class "Default")
      (node (ref "DD1") (pin "35") (pinfunction "PA2_(ADC2)_35") (pintype "bidirectional"))
      (node (ref "R6") (pin "2") (pinfunction "2_2") (pintype "passive"))
    )
    (net (code "45") (name "Net-(DD1-PA3_(ADC3))") (class "Default")
      (node (ref "DD1") (pin "34") (pinfunction "PA3_(ADC3)_34") (pintype "bidirectional"))
      (node (ref "R7") (pin "2") (pinfunction "2_2") (pintype "passive"))
    )
    (net (code "46") (name "Net-(DD1-PA4_(ADC4))") (class "Default")
      (node (ref "DD1") (pin "33") (pinfunction "PA4_(ADC4)_33") (pintype "bidirectional"))
      (node (ref "R8") (pin "2") (pinfunction "2_2") (pintype "passive"))
    )
    (net (code "47") (name "Net-(DD1-PA5_(ADC5))") (class "Default")
      (node (ref "DD1") (pin "32") (pinfunction "PA5_(ADC5)_32") (pintype "bidirectional"))
      (node (ref "R9") (pin "2") (pinfunction "2_2") (pintype "passive"))
    )
    (net (code "48") (name "Net-(DD1-PD6_(ICP1))") (class "Default")
      (node (ref "DD1") (pin "15") (pinfunction "PD6_(ICP1)_15") (pintype "bidirectional"))
      (node (ref "R13") (pin "1") (pinfunction "1_1") (pintype "passive"))
    )
    (net (code "49") (name "Net-(DD1-PD7_(OC2))") (class "Default")
      (node (ref "DD1") (pin "16") (pinfunction "PD7_(OC2)_16") (pintype "bidirectional"))
      (node (ref "R14") (pin "1") (pinfunction "1_1") (pintype "passive"))
    )
    (net (code "50") (name "Net-(DD2-PB0_(MOSI{slash}DI{slash}SDA{slash}AIN0{slash}OC0A{slash}~{OC1A}{slash}AREF{slash}PCINT0))") (class "Default")
      (node (ref "DD2") (pin "5") (pinfunction "PB0_(MOSI/DI/SDA/AIN0/OC0A/~{OC1A}/AREF/PCINT0)_5") (pintype "bidirectional"))
      (node (ref "Q1") (pin "1") (pinfunction "C_1") (pintype "passive"))
      (node (ref "R3") (pin "1") (pinfunction "1_1") (pintype "passive"))
    )
    (net (code "51") (name "Net-(DD2-PB4_(PCINT4{slash}XTAL2{slash}CLKO{slash}OC1B{slash}ADC2))") (class "Default")
      (node (ref "DD2") (pin "3") (pinfunction "PB4_(PCINT4/XTAL2/CLKO/OC1B/ADC2)_3") (pintype "bidirectional"))
      (node (ref "LD1") (pin "2") (pinfunction "K_2") (pintype "passive"))
    )
    (net (code "52") (name "Net-(DD2-PB5_(PCINT5{slash}~{RESET}{slash}ADC0{slash}DW))") (class "Default")
      (node (ref "C1") (pin "2") (pinfunction "2_2") (pintype "passive"))
      (node (ref "DD2") (pin "1") (pinfunction "PB5_(PCINT5/~{RESET}/ADC0/DW)_1") (pintype "bidirectional"))
      (node (ref "R4") (pin "1") (pinfunction "1_1") (pintype "passive"))
    )
    (net (code "53") (name "Net-(J1-E)") (class "Default")
      (node (ref "J1") (pin "3") (pinfunction "E_3") (pintype "power_in"))
      (node (ref "J2") (pin "3") (pinfunction "E_3") (pintype "power_in"))
      (node (ref "P9") (pin "3") (pinfunction "E_3") (pintype "power_in"))
      (node (ref "R38") (pin "2") (pinfunction "2_2") (pintype "passive"))
    )
    (net (code "54") (name "Net-(J1-L)") (class "Default")
      (node (ref "J1") (pin "1") (pinfunction "L_1") (pintype "power_in"))
      (node (ref "R35") (pin "2") (pinfunction "2_2") (pintype "passive"))
      (node (ref "U1") (pin "6") (pinfunction "B1_6") (pintype "passive"))
      (node (ref "VS1") (pin "1") (pinfunction "A_1") (pintype "passive"))
    )
    (net (code "55") (name "Net-(J2-L)") (class "Default")
      (node (ref "J2") (pin "1") (pinfunction "L_1") (pintype "power_in"))
      (node (ref "R45") (pin "2") (pinfunction "2_2") (pintype "passive"))
      (node (ref "R48") (pin "2") (pinfunction "2_2") (pintype "passive"))
      (node (ref "VS2") (pin "1") (pinfunction "A_1") (pintype "passive"))
    )
    (net (code "56") (name "Net-(LD1-A)") (class "Default")
      (node (ref "LD1") (pin "1") (pinfunction "A_1") (pintype "passive"))
      (node (ref "R5") (pin "1") (pinfunction "1_1") (pintype "passive"))
    )
    (net (code "57") (name "Net-(LD2-A)") (class "Default")
      (node (ref "C11") (pin "1") (pinfunction "1_1") (pintype "passive"))
      (node (ref "LD2") (pin "1") (pinfunction "A_1") (pintype "passive"))
      (node (ref "VD10") (pin "2") (pinfunction "K_2") (pintype "passive"))
    )
    (net (code "58") (name "Net-(P1-Pad3)") (class "Default")
      (node (ref "P1") (pin "3") (pinfunction "3_3") (pintype "passive"))
      (node (ref "P1") (pin "4") (pinfunction "4_4") (pintype "passive"))
      (node (ref "R11") (pin "1") (pinfunction "1_1") (pintype "passive"))
    )
    (net (code "59") (name "Net-(P6-Pad1)") (class "Default")
      (node (ref "P6") (pin "1") (pinfunction "1_1") (pintype "passive"))
      (node (ref "R23") (pin "2") (pinfunction "2_2") (pintype "passive"))
    )
    (net (code "60") (name "Net-(P6-Pad2)") (class "Default")
      (node (ref "P6") (pin "2") (pinfunction "2_2") (pintype "passive"))
      (node (ref "R24") (pin "2") (pinfunction "2_2") (pintype "passive"))
    )
    (net (code "61") (name "Net-(P6-Pad3)") (class "Default")
      (node (ref "P6") (pin "3") (pinfunction "3_3") (pintype "passive"))
      (node (ref "R25") (pin "2") (pinfunction "2_2") (pintype "passive"))
    )
    (net (code "62") (name "Net-(P6-Pad4)") (class "Default")
      (node (ref "P6") (pin "4") (pinfunction "4_4") (pintype "passive"))
      (node (ref "R26") (pin "2") (pinfunction "2_2") (pintype "passive"))
    )
    (net (code "63") (name "Net-(P6-Pad5)") (class "Default")
      (node (ref "P6") (pin "5") (pinfunction "5_5") (pintype "passive"))
      (node (ref "R27") (pin "2") (pinfunction "2_2") (pintype "passive"))
    )
    (net (code "64") (name "Net-(P6-Pad6)") (class "Default")
      (node (ref "P6") (pin "6") (pinfunction "6_6") (pintype "passive"))
      (node (ref "R28") (pin "2") (pinfunction "2_2") (pintype "passive"))
    )
    (net (code "65") (name "Net-(P6-Pad7)") (class "Default")
      (node (ref "P6") (pin "7") (pinfunction "7_7") (pintype "passive"))
      (node (ref "R29") (pin "2") (pinfunction "2_2") (pintype "passive"))
    )
    (net (code "66") (name "Net-(P6-Pad8)") (class "Default")
      (node (ref "P6") (pin "8") (pinfunction "8_8") (pintype "passive"))
      (node (ref "R30") (pin "2") (pinfunction "2_2") (pintype "passive"))
    )
    (net (code "67") (name "Net-(Q1-B)") (class "Default")
      (node (ref "Q1") (pin "2") (pinfunction "B_2") (pintype "passive"))
      (node (ref "R10") (pin "2") (pinfunction "2_2") (pintype "passive"))
      (node (ref "R12") (pin "2") (pinfunction "2_2") (pintype "passive"))
    )
    (net (code "68") (name "Net-(Q2-B)") (class "Default")
      (node (ref "Q2") (pin "2") (pinfunction "B_2") (pintype "passive"))
      (node (ref "R15") (pin "2") (pinfunction "2_2") (pintype "passive"))
      (node (ref "R17") (pin "2") (pinfunction "2_2") (pintype "passive"))
    )
    (net (code "69") (name "Net-(Q2-C)") (class "Default")
      (node (ref "P3") (pin "1") (pinfunction "1_1") (pintype "passive"))
      (node (ref "Q2") (pin "1") (pinfunction "C_1") (pintype "passive"))
    )
    (net (code "70") (name "Net-(Q3-B)") (class "Default")
      (node (ref "Q3") (pin "2") (pinfunction "B_2") (pintype "passive"))
      (node (ref "R16") (pin "2") (pinfunction "2_2") (pintype "passive"))
      (node (ref "R18") (pin "2") (pinfunction "2_2") (pintype "passive"))
    )
    (net (code "71") (name "Net-(Q3-C)") (class "Default")
      (node (ref "P3") (pin "3") (pinfunction "3_3") (pintype "passive"))
      (node (ref "Q3") (pin "1") (pinfunction "C_1") (pintype "passive"))
    )
    (net (code "72") (name "Net-(Q4-B)") (class "Default")
      (node (ref "Q4") (pin "2") (pinfunction "B_2") (pintype "passive"))
      (node (ref "R19") (pin "2") (pinfunction "2_2") (pintype "passive"))
      (node (ref "R21") (pin "2") (pinfunction "2_2") (pintype "passive"))
    )
    (net (code "73") (name "Net-(Q4-C)") (class "Default")
      (node (ref "P3") (pin "2") (pinfunction "2_2") (pintype "passive"))
      (node (ref "Q4") (pin "1") (pinfunction "C_1") (pintype "passive"))
    )
    (net (code "74") (name "Net-(Q5-B)") (class "Default")
      (node (ref "Q5") (pin "2") (pinfunction "B_2") (pintype "passive"))
      (node (ref "R20") (pin "2") (pinfunction "2_2") (pintype "passive"))
      (node (ref "R22") (pin "2") (pinfunction "2_2") (pintype "passive"))
    )
    (net (code "75") (name "Net-(Q5-C)") (class "Default")
      (node (ref "P3") (pin "4") (pinfunction "4_4") (pintype "passive"))
      (node (ref "Q5") (pin "1") (pinfunction "C_1") (pintype "passive"))
    )
    (net (code "76") (name "Net-(Q6-B)") (class "Default")
      (node (ref "Q6") (pin "2") (pinfunction "B_2") (pintype "passive"))
      (node (ref "R39") (pin "2") (pinfunction "2_2") (pintype "passive"))
      (node (ref "R40") (pin "2") (pinfunction "2_2") (pintype "passive"))
    )
    (net (code "77") (name "Net-(Q6-C)") (class "Default")
      (node (ref "Q6") (pin "1") (pinfunction "C_1") (pintype "passive"))
      (node (ref "U1") (pin "2") (pinfunction "A2_2") (pintype "passive"))
    )
    (net (code "78") (name "Net-(Q7-B)") (class "Default")
      (node (ref "Q7") (pin "2") (pinfunction "B_2") (pintype "passive"))
      (node (ref "R47") (pin "2") (pinfunction "2_2") (pintype "passive"))
      (node (ref "R49") (pin "2") (pinfunction "2_2") (pintype "passive"))
    )
    (net (code "79") (name "Net-(Q7-C)") (class "Default")
      (node (ref "LS1") (pin "2") (pinfunction "2_2") (pintype "passive"))
      (node (ref "LS1") (pin "2A") (pinfunction "2A_2A") (pintype "passive"))
      (node (ref "Q7") (pin "1") (pinfunction "C_1") (pintype "passive"))
    )
    (net (code "80") (name "Net-(R46-BOT)") (class "Default")
      (node (ref "C11") (pin "2") (pinfunction "2_2") (pintype "passive"))
      (node (ref "R46") (pin "2") (pinfunction "BOT_2") (pintype "passive"))
      (node (ref "VD9") (pin "1") (pinfunction "A_1") (pintype "passive"))
    )
    (net (code "81") (name "Net-(R46-TAP)") (class "Default")
      (node (ref "R45") (pin "1") (pinfunction "1_1") (pintype "passive"))
      (node (ref "R46") (pin "1") (pinfunction "TOP_1") (pintype "passive"))
      (node (ref "R46") (pin "3") (pinfunction "TAP_3") (pintype "passive"))
    )
    (net (code "82") (name "Net-(U1-A1)") (class "Default")
      (node (ref "R31") (pin "2") (pinfunction "2_2") (pintype "passive"))
      (node (ref "U1") (pin "1") (pinfunction "A1_1") (pintype "passive"))
    )
    (net (code "83") (name "Net-(U1-B3)") (class "Default")
      (node (ref "R37") (pin "2") (pinfunction "2_2") (pintype "passive"))
      (node (ref "U1") (pin "4") (pinfunction "B3_4") (pintype "passive"))
    )
    (net (code "84") (name "Net-(VD1-A)") (class "Default")
      (node (ref "R11") (pin "2") (pinfunction "2_2") (pintype "passive"))
      (node (ref "VD1") (pin "2") (pinfunction "A_2") (pintype "passive"))
    )
    (net (code "85") (name "Net-(VD1-K)") (class "Default")
      (node (ref "R10") (pin "1") (pinfunction "1_1") (pintype "passive"))
      (node (ref "VD1") (pin "1") (pinfunction "K_1") (pintype "passive"))
      (node (ref "VD2") (pin "1") (pinfunction "K_1") (pintype "passive"))
    )
    (net (code "86") (name "Net-(VD3-K)") (class "Default")
      (node (ref "P4") (pin "1") (pinfunction "1_1") (pintype "passive"))
      (node (ref "P4") (pin "2") (pinfunction "2_2") (pintype "passive"))
      (node (ref "VD3") (pin "1") (pinfunction "K_1") (pintype "passive"))
      (node (ref "VD5") (pin "2") (pinfunction "A_2") (pintype "passive"))
    )
    (net (code "87") (name "Net-(VD4-K)") (class "Default")
      (node (ref "P4") (pin "5") (pinfunction "5_5") (pintype "passive"))
      (node (ref "P4") (pin "6") (pinfunction "6_6") (pintype "passive"))
      (node (ref "VD4") (pin "1") (pinfunction "K_1") (pintype "passive"))
      (node (ref "VD6") (pin "2") (pinfunction "A_2") (pintype "passive"))
    )
    (net (code "88") (name "Net-(VD7-A)") (class "Default")
      (node (ref "R32") (pin "2") (pinfunction "2_2") (pintype "passive"))
      (node (ref "VD7") (pin "1") (pinfunction "A_1") (pintype "passive"))
    )
    (net (code "89") (name "Net-(VD8-A)") (class "Default")
      (node (ref "R36") (pin "2") (pinfunction "2_2") (pintype "passive"))
      (node (ref "VD8") (pin "1") (pinfunction "A_1") (pintype "passive"))
    )
    (net (code "90") (name "Net-(VD9-K)") (class "Default")
      (node (ref "VD9") (pin "2") (pinfunction "K_2") (pintype "passive"))
      (node (ref "VS2") (pin "2") (pinfunction "G_2") (pintype "passive"))
    )
    (net (code "91") (name "Net-(VS1-G)") (class "Default")
      (node (ref "R37") (pin "1") (pinfunction "1_1") (pintype "passive"))
      (node (ref "VS1") (pin "2") (pinfunction "G_2") (pintype "passive"))
    )
    (net (code "92") (name "VCC") (class "Default")
      (node (ref "C16") (pin "1") (pinfunction "1_1") (pintype "passive"))
      (node (ref "C18") (pin "2") (pinfunction "2_2") (pintype "passive"))
      (node (ref "C2") (pin "2") (pinfunction "2_2") (pintype "passive"))
      (node (ref "C7") (pin "2") (pinfunction "2_2") (pintype "passive"))
      (node (ref "C8") (pin "2") (pinfunction "2_2") (pintype "passive"))
      (node (ref "C9") (pin "2") (pinfunction "2_2") (pintype "passive"))
      (node (ref "DA1") (pin "8") (pinfunction "V+_8") (pintype "power_in"))
      (node (ref "DD1") (pin "17") (pinfunction "VCC_17") (pintype "power_in"))
      (node (ref "DD1") (pin "38") (pinfunction "VCC_38") (pintype "power_in"))
      (node (ref "DD1") (pin "5") (pinfunction "VCC_5") (pintype "power_in"))
      (node (ref "DD2") (pin "8") (pinfunction "VCC_8") (pintype "power_in"))
      (node (ref "LS1") (pin "1") (pinfunction "1_1") (pintype "passive"))
      (node (ref "LS1") (pin "1A") (pinfunction "1A_1A") (pintype "passive"))
      (node (ref "P2") (pin "2") (pinfunction "2_2") (pintype "passive"))
      (node (ref "P5") (pin "1") (pinfunction "1_1") (pintype "passive"))
      (node (ref "P8") (pin "13") (pinfunction "13_13") (pintype "passive"))
      (node (ref "R3") (pin "2") (pinfunction "2_2") (pintype "passive"))
      (node (ref "R31") (pin "1") (pinfunction "1_1") (pintype "passive"))
      (node (ref "R33") (pin "2") (pinfunction "2_2") (pintype "passive"))
      (node (ref "R34") (pin "2") (pinfunction "2_2") (pintype "passive"))
      (node (ref "R4") (pin "2") (pinfunction "2_2") (pintype "passive"))
      (node (ref "R43") (pin "1") (pinfunction "1_1") (pintype "passive"))
      (node (ref "R44") (pin "2") (pinfunction "2_2") (pintype "passive"))
      (node (ref "R5") (pin "2") (pinfunction "2_2") (pintype "passive"))
      (node (ref "U2") (pin "3") (pinfunction "OUT_3") (pintype "power_in"))
    )
    (net (code "93") (name "Vcc+10V") (class "Default")
      (node (ref "C14") (pin "1") (pinfunction "1_1") (pintype "passive"))
      (node (ref "C15") (pin "1") (pinfunction "1_1") (pintype "passive"))
      (node (ref "C17") (pin "2") (pinfunction "2_2") (pintype "passive"))
      (node (ref "U2") (pin "1") (pinfunction "IN_1") (pintype "power_in"))
      (node (ref "VD3") (pin "2") (pinfunction "A_2") (pintype "passive"))
      (node (ref "VD4") (pin "2") (pinfunction "A_2") (pintype "passive"))
    )
    (net (code "94") (name "unconnected-(DD1-PA6_(ADC6)-Pad31)") (class "Default")
      (node (ref "DD1") (pin "31") (pinfunction "PA6_(ADC6)_31") (pintype "bidirectional"))
    )
    (net (code "95") (name "unconnected-(DD1-PA7_(ADC7)-Pad30)") (class "Default")
      (node (ref "DD1") (pin "30") (pinfunction "PA7_(ADC7)_30") (pintype "bidirectional"))
    )
    (net (code "96") (name "unconnected-(DD1-PB4_(~{SS})-Pad44)") (class "Default")
      (node (ref "DD1") (pin "44") (pinfunction "PB4_(~{SS})_44") (pintype "bidirectional"))
    )
    (net (code "97") (name "unconnected-(DD2-PB2_(SCK{slash}USCK{slash}SCL{slash}ADC1{slash}T0{slash}INT0{slash}PCINT2)-Pad7)") (class "Default")
      (node (ref "DD2") (pin "7") (pinfunction "PB2_(SCK/USCK/SCL/ADC1/T0/INT0/PCINT2)_7") (pintype "bidirectional"))
    )
    (net (code "98") (name "unconnected-(DD2-PB3_(PCINT3{slash}XTAL1{slash}CLKI{slash}~{OC1B}{slash}ADC3)-Pad2)") (class "Default")
      (node (ref "DD2") (pin "2") (pinfunction "PB3_(PCINT3/XTAL1/CLKI/~{OC1B}/ADC3)_2") (pintype "bidirectional"))
    )
    (net (code "99") (name "unconnected-(P2-Pad3)") (class "Default")
      (node (ref "P2") (pin "3") (pinfunction "3_3") (pintype "passive"))
    )
    (net (code "100") (name "unconnected-(U1-A3-Pad3)") (class "Default")
      (node (ref "U1") (pin "3") (pinfunction "A3_3") (pintype "passive"))
    )
    (net (code "101") (name "unconnected-(U1-B2-Pad5)") (class "Default")
      (node (ref "U1") (pin "5") (pinfunction "B2_5") (pintype "passive"))
    )
  )
)
